# MagRes_Sensor.net
KiCad netlist of a schematic drawn in EAGLE
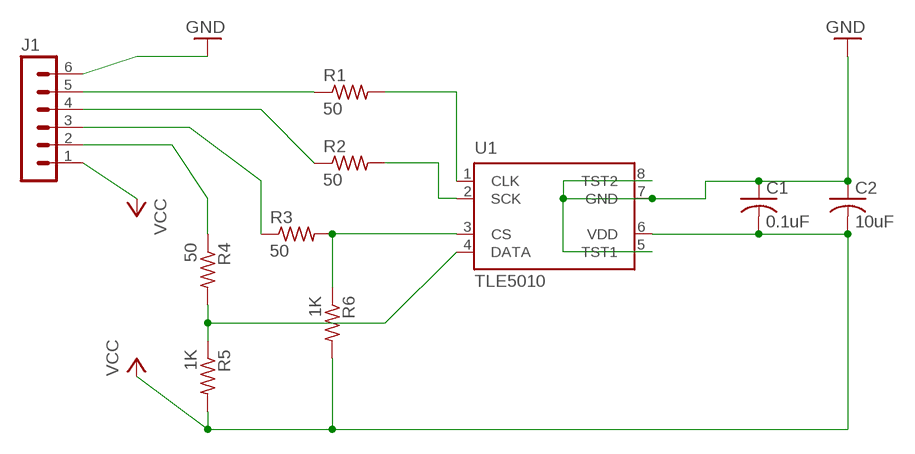
[diagram p0: schematic, sheet 1]

(export (version "E")
  (design (tool "Eeschema 10.0.6"))
  (components
    (comp (ref "C1")
      (value "0.1uF")
      (footprint "eagle-import:C1206")
      (libsource (lib "eagle-import") (part "C-USC1206"))
    )
    (comp (ref "C2")
      (value "10uF")
      (footprint "eagle-import:C1206")
      (libsource (lib "eagle-import") (part "C-USC1206"))
    )
    (comp (ref "J1")
      (value "MA06-1")
      (footprint "eagle-import:MA06-1")
      (libsource (lib "eagle-import") (part "MA06-1"))
    )
    (comp (ref "R1")
      (value "50")
      (footprint "eagle-import:R1206")
      (libsource (lib "eagle-import") (part "R-US_R1206"))
    )
    (comp (ref "R2")
      (value "50")
      (footprint "eagle-import:R1206")
      (libsource (lib "eagle-import") (part "R-US_R1206"))
    )
    (comp (ref "R3")
      (value "50")
      (footprint "eagle-import:R1206")
      (libsource (lib "eagle-import") (part "R-US_R1206"))
    )
    (comp (ref "R4")
      (value "50")
      (footprint "eagle-import:R1206")
      (libsource (lib "eagle-import") (part "R-US_R1206"))
    )
    (comp (ref "R5")
      (value "1K")
      (footprint "eagle-import:R1206")
      (libsource (lib "eagle-import") (part "R-US_R1206"))
    )
    (comp (ref "R6")
      (value "1K")
      (footprint "eagle-import:R1206")
      (libsource (lib "eagle-import") (part "R-US_R1206"))
    )
    (comp (ref "U1")
      (value "TLE5010")
      (footprint "eagle-import:PG-DSO-8")
      (libsource (lib "eagle-import") (part "TLE5010"))
    )
  )
  (nets
    (net (code "1") (name "GND") (class "Default")
      (node (ref "C1") (pin "1") (pinfunction "1_1") (pintype "passive"))
      (node (ref "C2") (pin "1") (pinfunction "1_1") (pintype "passive"))
      (node (ref "J1") (pin "6") (pinfunction "6_6") (pintype "passive"))
      (node (ref "U1") (pin "5") (pinfunction "TST1_5") (pintype "bidirectional"))
      (node (ref "U1") (pin "7") (pinfunction "GND_7") (pintype "power_in"))
      (node (ref "U1") (pin "8") (pinfunction "TST2_8") (pintype "bidirectional"))
    )
    (net (code "2") (name "Net-(J1-Pad2)") (class "Default")
      (node (ref "J1") (pin "2") (pinfunction "2_2") (pintype "passive"))
      (node (ref "R4") (pin "1") (pinfunction "1_1") (pintype "passive"))
    )
    (net (code "3") (name "Net-(J1-Pad3)") (class "Default")
      (node (ref "J1") (pin "3") (pinfunction "3_3") (pintype "passive"))
      (node (ref "R3") (pin "1") (pinfunction "1_1") (pintype "passive"))
    )
    (net (code "4") (name "Net-(J1-Pad4)") (class "Default")
      (node (ref "J1") (pin "4") (pinfunction "4_4") (pintype "passive"))
      (node (ref "R2") (pin "1") (pinfunction "1_1") (pintype "passive"))
    )
    (net (code "5") (name "Net-(J1-Pad5)") (class "Default")
      (node (ref "J1") (pin "5") (pinfunction "5_5") (pintype "passive"))
      (node (ref "R1") (pin "1") (pinfunction "1_1") (pintype "passive"))
    )
    (net (code "6") (name "Net-(U1-CLK)") (class "Default")
      (node (ref "R1") (pin "2") (pinfunction "2_2") (pintype "passive"))
      (node (ref "U1") (pin "1") (pinfunction "CLK_1") (pintype "input"))
    )
    (net (code "7") (name "Net-(U1-CS)") (class "Default")
      (node (ref "R3") (pin "2") (pinfunction "2_2") (pintype "passive"))
      (node (ref "R6") (pin "1") (pinfunction "1_1") (pintype "passive"))
      (node (ref "U1") (pin "3") (pinfunction "CS_3") (pintype "input"))
    )
    (net (code "8") (name "Net-(U1-DATA)") (class "Default")
      (node (ref "R4") (pin "2") (pinfunction "2_2") (pintype "passive"))
      (node (ref "R5") (pin "1") (pinfunction "1_1") (pintype "passive"))
      (node (ref "U1") (pin "4") (pinfunction "DATA_4") (pintype "bidirectional"))
    )
    (net (code "9") (name "Net-(U1-SCK)") (class "Default")
      (node (ref "R2") (pin "2") (pinfunction "2_2") (pintype "passive"))
      (node (ref "U1") (pin "2") (pinfunction "SCK_2") (pintype "input"))
    )
    (net (code "10") (name "VCC") (class "Default")
      (node (ref "C1") (pin "2") (pinfunction "2_2") (pintype "passive"))
      (node (ref "C2") (pin "2") (pinfunction "2_2") (pintype "passive"))
      (node (ref "J1") (pin "1") (pinfunction "1_1") (pintype "passive"))
      (node (ref "R5") (pin "2") (pinfunction "2_2") (pintype "passive"))
      (node (ref "R6") (pin "2") (pinfunction "2_2") (pintype "passive"))
      (node (ref "U1") (pin "6") (pinfunction "VDD_6") (pintype "power_in"))
    )
  )
)
